# C210_0006_Power.net
KiCad netlist of a schematic drawn in Altium Designer
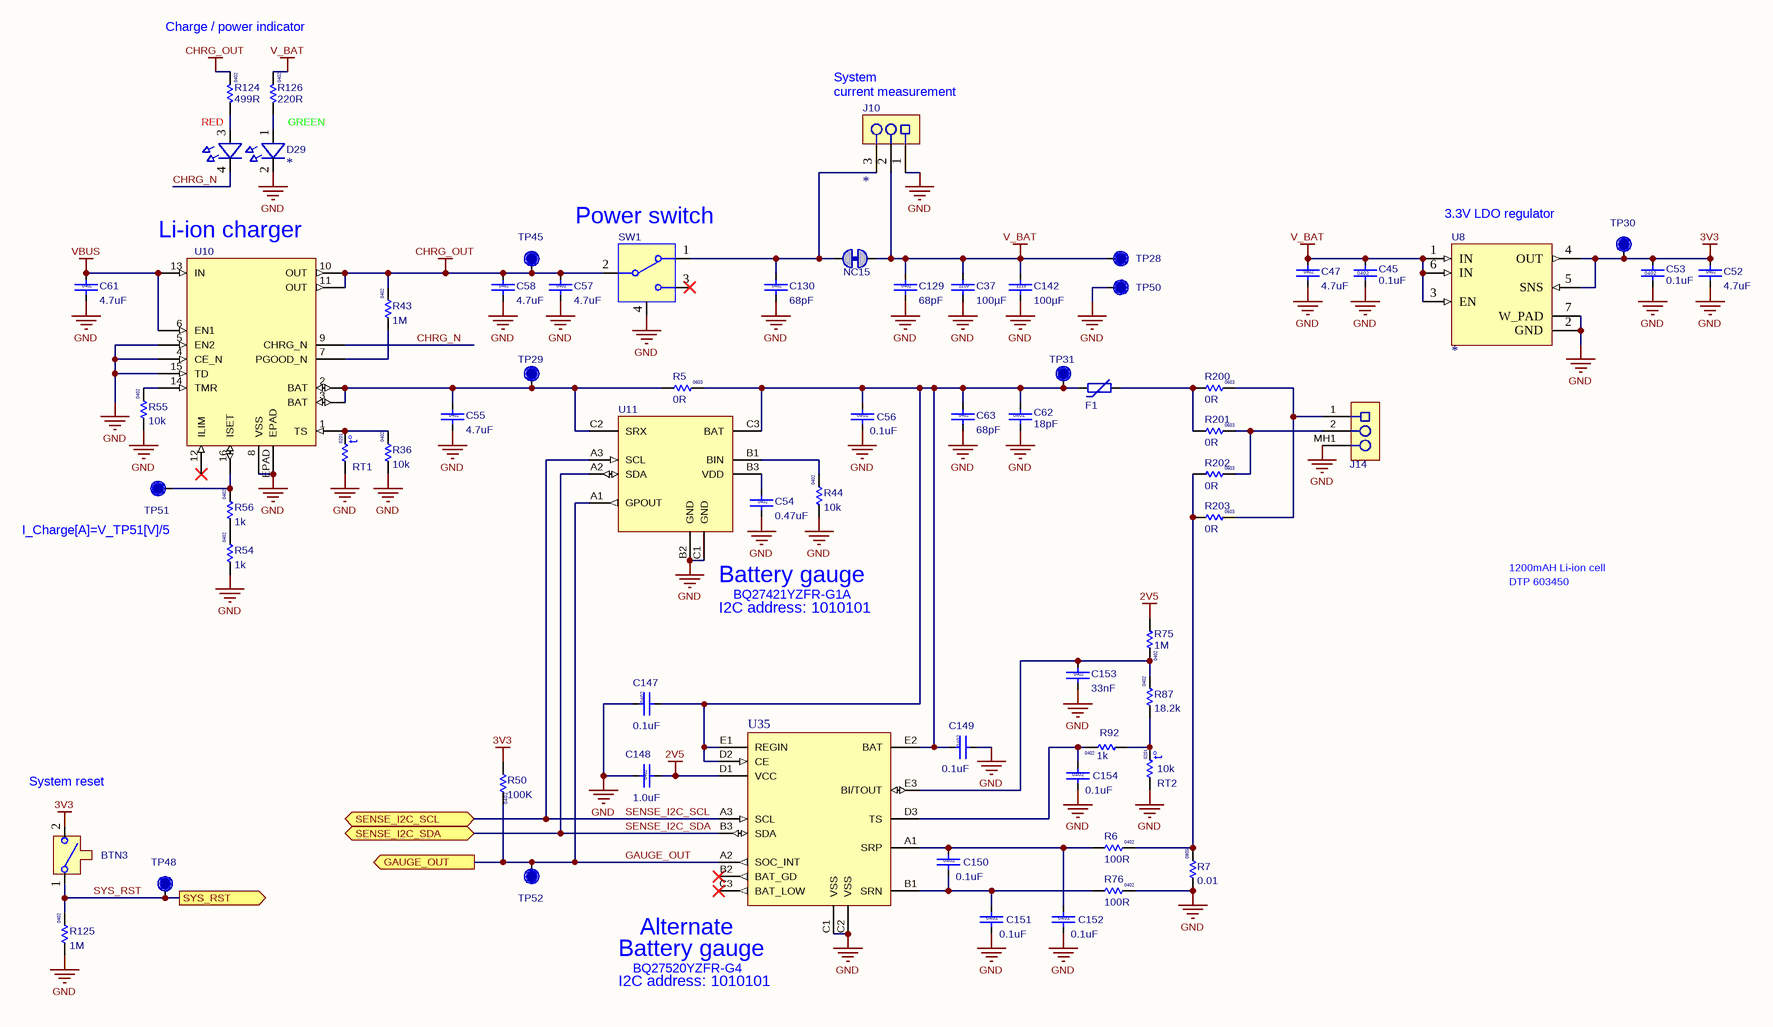
[diagram p0: C210_0006_Power.SchDoc]

(export (version "E")
  (design (tool "Eeschema 10.0.6"))
  (components
    (comp (ref "BTN3")
      (value "135-00006")
      (footprint "B3U-3000P")
      (description "Button SPST-NO Off-MOM, 50mA 12V, Right Angle, SMT")
      (fields (field (name "VOLTAGE") "12VDC"))
      (libsource (lib "Arena_Parts_DB_Lib") (part "SW_SPST"))
    )
    (comp (ref "C37")
      (value "100µF")
      (footprint "Cap 1210")
      (description "100µF ±20% 10V Ceramic Capacitor X5R 1210 (3225 Metric)")
      (fields
        (field (name "SIZE") "1210")
        (field (name "PART NUMBER") "120-00223")
        (field (name "TOLERANCE") "+/- 20%")
      )
      (libsource (lib "Arena_Parts_DB_Lib") (part "Cap Chip"))
    )
    (comp (ref "C45")
      (value "0.1uF")
      (footprint "Cap 0402 HD")
      (description "Cap, Ceramic 0.1uF 10V 10% X5R 0402")
      (fields
        (field (name "SIZE") "0402")
        (field (name "PART NUMBER") "120-00016")
        (field (name "MANUFACTURER") "Murata Electronics North America")
      )
      (libsource (lib "Arena_Parts_DB_Lib") (part "Cap Chip"))
    )
    (comp (ref "C47")
      (value "4.7uF")
      (footprint "Cap 0402 HD")
      (description "Cap, Ceramic 4.7uF 10V 20% X5R 0402")
      (fields
        (field (name "SIZE") "0402")
        (field (name "PART NUMBER") "120-00020")
        (field (name "TOLERANCE") "+/- 20%")
      )
      (libsource (lib "Arena_Parts_DB_Lib") (part "Cap Chip"))
    )
    (comp (ref "C52")
      (value "4.7uF")
      (footprint "Cap 0402 HD")
      (description "Cap, Ceramic 4.7uF 10V 20% X5R 0402")
      (fields
        (field (name "SIZE") "0402")
        (field (name "PART NUMBER") "120-00020")
        (field (name "TOLERANCE") "+/- 20%")
      )
      (libsource (lib "Arena_Parts_DB_Lib") (part "Cap Chip"))
    )
    (comp (ref "C53")
      (value "0.1uF")
      (footprint "Cap 0402 HD")
      (description "Cap, Ceramic 0.1uF 10V 10% X5R 0402")
      (fields
        (field (name "SIZE") "0402")
        (field (name "PART NUMBER") "120-00016")
        (field (name "MANUFACTURER") "Murata Electronics North America")
      )
      (libsource (lib "Arena_Parts_DB_Lib") (part "Cap Chip"))
    )
    (comp (ref "C54")
      (value "0.47uF")
      (footprint "Cap 0402 HD")
      (description "Cap, Ceramic, 0.47UF 10V 10% X5R 0402")
      (fields
        (field (name "SIZE") "0402")
        (field (name "PART NUMBER") "120-00072")
        (field (name "TOLERANCE") "+/- 10%")
      )
      (libsource (lib "Arena_Parts_DB_Lib") (part "Cap Chip"))
    )
    (comp (ref "C55")
      (value "4.7uF")
      (footprint "Cap 0402 HD")
      (description "Cap, Ceramic 4.7uF 10V 20% X5R 0402")
      (fields
        (field (name "SIZE") "0402")
        (field (name "PART NUMBER") "120-00020")
        (field (name "TOLERANCE") "+/- 20%")
      )
      (libsource (lib "Arena_Parts_DB_Lib") (part "Cap Chip"))
    )
    (comp (ref "C56")
      (value "0.1uF")
      (footprint "Cap 0402 HD")
      (description "Cap, Ceramic 0.1uF 10V 10% X5R 0402")
      (fields
        (field (name "SIZE") "0402")
        (field (name "PART NUMBER") "120-00016")
        (field (name "MANUFACTURER") "Murata Electronics North America")
      )
      (libsource (lib "Arena_Parts_DB_Lib") (part "Cap Chip"))
    )
    (comp (ref "C57")
      (value "4.7uF")
      (footprint "Cap 0402 HD")
      (description "Cap, Ceramic 4.7uF 10V 20% X5R 0402")
      (fields
        (field (name "SIZE") "0402")
        (field (name "PART NUMBER") "120-00020")
        (field (name "TOLERANCE") "+/- 20%")
      )
      (libsource (lib "Arena_Parts_DB_Lib") (part "Cap Chip"))
    )
    (comp (ref "C58")
      (value "4.7uF")
      (footprint "Cap 0402 HD")
      (description "Cap, Ceramic 4.7uF 10V 20% X5R 0402")
      (fields
        (field (name "SIZE") "0402")
        (field (name "PART NUMBER") "120-00020")
        (field (name "TOLERANCE") "+/- 20%")
      )
      (libsource (lib "Arena_Parts_DB_Lib") (part "Cap Chip"))
    )
    (comp (ref "C61")
      (value "4.7uF")
      (footprint "Cap 0402 HD")
      (description "Cap, Ceramic 4.7uF 10V 20% X5R 0402")
      (fields
        (field (name "SIZE") "0402")
        (field (name "PART NUMBER") "120-00020")
        (field (name "TOLERANCE") "+/- 20%")
      )
      (libsource (lib "Arena_Parts_DB_Lib") (part "Cap Chip"))
    )
    (comp (ref "C62")
      (value "18pF")
      (footprint "Cap 0402 HD")
      (description "Cap, Ceramic 18pF 50V 5% NP0 0402")
      (fields
        (field (name "SIZE") "0402")
        (field (name "PART NUMBER") "120-00041")
        (field (name "TOLERANCE") "+/- 5%")
      )
      (libsource (lib "Arena_Parts_DB_Lib") (part "Cap Chip"))
    )
    (comp (ref "C63")
      (value "68pF")
      (footprint "Cap 0402 HD")
      (description "Cap, Ceramic, 68pF, 50V, 1%, NP0, 0402")
      (fields
        (field (name "SIZE") "0402")
        (field (name "PART NUMBER") "120-00047")
        (field (name "TOLERANCE") "+/- 1%")
      )
      (libsource (lib "Arena_Parts_DB_Lib") (part "Cap Chip"))
    )
    (comp (ref "C129")
      (value "68pF")
      (footprint "Cap 0402 HD")
      (description "Cap, Ceramic, 68pF, 50V, 1%, NP0, 0402")
      (fields
        (field (name "SIZE") "0402")
        (field (name "PART NUMBER") "120-00047")
        (field (name "TOLERANCE") "+/- 1%")
      )
      (libsource (lib "Arena_Parts_DB_Lib") (part "Cap Chip"))
    )
    (comp (ref "C130")
      (value "68pF")
      (footprint "Cap 0402 HD")
      (description "Cap, Ceramic, 68pF, 50V, 1%, NP0, 0402")
      (fields
        (field (name "SIZE") "0402")
        (field (name "PART NUMBER") "120-00047")
        (field (name "TOLERANCE") "+/- 1%")
      )
      (libsource (lib "Arena_Parts_DB_Lib") (part "Cap Chip"))
    )
    (comp (ref "C142")
      (value "100µF")
      (footprint "Cap 1210")
      (description "100µF ±20% 10V Ceramic Capacitor X5R 1210 (3225 Metric)")
      (fields
        (field (name "SIZE") "1210")
        (field (name "PART NUMBER") "120-00223")
        (field (name "TOLERANCE") "+/- 20%")
      )
      (libsource (lib "Arena_Parts_DB_Lib") (part "Cap Chip"))
    )
    (comp (ref "C147")
      (value "0.1uF")
      (footprint "Cap 0402 HD")
      (description "Cap, Ceramic 0.1uF 10V 10% X5R 0402")
      (fields
        (field (name "SIZE") "0402")
        (field (name "PART NUMBER") "120-00016")
        (field (name "MANUFACTURER") "Murata Electronics North America")
      )
      (libsource (lib "Arena_Parts_DB_Lib") (part "Cap Chip"))
    )
    (comp (ref "C148")
      (value "1.0uF")
      (footprint "Cap 0402 HD")
      (description "Cap, Ceramic, 1.0uF 10V 10% X5R, 0402")
      (fields
        (field (name "SIZE") "0402")
        (field (name "PART NUMBER") "120-00017")
        (field (name "MANUFACTURER") "Murata Electronics North America")
      )
      (libsource (lib "Arena_Parts_DB_Lib") (part "Cap Chip"))
    )
    (comp (ref "C149")
      (value "0.1uF")
      (footprint "Cap 0402 HD")
      (description "Cap, Ceramic 0.1uF 10V 10% X5R 0402")
      (fields
        (field (name "SIZE") "0402")
        (field (name "PART NUMBER") "120-00016")
        (field (name "MANUFACTURER") "Murata Electronics North America")
      )
      (libsource (lib "Arena_Parts_DB_Lib") (part "Cap Chip"))
    )
    (comp (ref "C150")
      (value "0.1uF")
      (footprint "Cap 0402 HD")
      (description "Cap, Ceramic 0.1uF 10V 10% X5R 0402")
      (fields
        (field (name "SIZE") "0402")
        (field (name "PART NUMBER") "120-00016")
        (field (name "MANUFACTURER") "Murata Electronics North America")
      )
      (libsource (lib "Arena_Parts_DB_Lib") (part "Cap Chip"))
    )
    (comp (ref "C151")
      (value "0.1uF")
      (footprint "Cap 0402 HD")
      (description "Cap, Ceramic 0.1uF 10V 10% X5R 0402")
      (fields
        (field (name "SIZE") "0402")
        (field (name "PART NUMBER") "120-00016")
        (field (name "MANUFACTURER") "Murata Electronics North America")
      )
      (libsource (lib "Arena_Parts_DB_Lib") (part "Cap Chip"))
    )
    (comp (ref "C152")
      (value "0.1uF")
      (footprint "Cap 0402 HD")
      (description "Cap, Ceramic 0.1uF 10V 10% X5R 0402")
      (fields
        (field (name "SIZE") "0402")
        (field (name "PART NUMBER") "120-00016")
        (field (name "MANUFACTURER") "Murata Electronics North America")
      )
      (libsource (lib "Arena_Parts_DB_Lib") (part "Cap Chip"))
    )
    (comp (ref "C153")
      (value "33nF")
      (footprint "Cap 0402 HD")
      (description "Cap, Ceramic 33nF 16V 10% X7R 0402")
      (fields
        (field (name "SIZE") "0402")
        (field (name "PART NUMBER") "120-00080")
        (field (name "TOLERANCE") "+/- 10%")
      )
      (libsource (lib "Arena_Parts_DB_Lib") (part "Cap Chip"))
    )
    (comp (ref "C154")
      (value "0.1uF")
      (footprint "Cap 0402 HD")
      (description "Cap, Ceramic 0.1uF 10V 10% X5R 0402")
      (fields
        (field (name "SIZE") "0402")
        (field (name "PART NUMBER") "120-00016")
        (field (name "MANUFACTURER") "Murata Electronics North America")
      )
      (libsource (lib "Arena_Parts_DB_Lib") (part "Cap Chip"))
    )
    (comp (ref "D29")
      (value "115-00013")
      (footprint "LED_4Pin_4213_RA_3215")
      (description "Dual LED, Red/Green, Right Angle, Dome 1208")
      (fields (field (name "COLOR") "*") (field (name "VOLTAGE") "None"))
      (libsource (lib "Arena_Parts_DB_Lib") (part "LED_Dual_1"))
    )
    (comp (ref "F1")
      (value "190-00005")
      (footprint "Fuse 1206")
      (description "Fuse, PTC 8V, 750mA, hold, 1.5A trip, 1206")
      (fields (field (name "VOLTAGE") "None"))
      (libsource (lib "Arena_Parts_DB_Lib") (part "PTC_Fuse"))
    )
    (comp (ref "J10")
      (value "130-00105")
      (footprint "HDR-0.1P-3Pin-1Row-SMT")
      (description "Header, 0.100\" Pitch, 3 Pin, Vertical SMT, Black")
      (fields (field (name "MANUFACTURER P/N") "*") (field (name "VOLTAGE") "None"))
      (libsource (lib "Arena_Parts_DB_Lib") (part "CON-3Pin_1Row"))
    )
    (comp (ref "J14")
      (value "S2B-PH-SM4-TB")
      (footprint "S2B-PH-SM4-TB")
      (description "Conn, SMT, 0.079\" Pitch, 2 Pin, R/A, Black")
      (fields (field (name "VOLTAGE") "None"))
      (libsource (lib "S2B-PH-SM4-TB") (part "S2B-PH-SM4-TB"))
    )
    (comp (ref "NC15")
      (value "Solderbridge-ShortDNP")
      (footprint "Solderbridge-Short")
      (description "Solderbridge-Short")
      (fields (field (name "ADDED BY") "Paul B"))
      (libsource (lib "PCB_Misc") (part "Solderbridge-Short"))
    )
    (comp (ref "R5")
      (value "0R")
      (footprint "RES 0603 HD")
      (description "Resistor 0 ohm Jumper, 1/10W, 0603")
      (fields
        (field (name "SIZE") "0603")
        (field (name "PART NUMBER") "180-00012")
        (field (name "POWER") "1/10W")
      )
      (libsource (lib "Arena_Parts_DB_Lib") (part "Res sm"))
    )
    (comp (ref "R6")
      (value "100R")
      (footprint "RES 0402 HD")
      (description "Resistor, 100ohm, 1%, 1/16W, 0402.")
      (fields
        (field (name "SIZE") "0402")
        (field (name "PART NUMBER") "180-00051")
        (field (name "POWER") "1/16W")
      )
      (libsource (lib "Arena_Parts_DB_Lib") (part "Res sm"))
    )
    (comp (ref "R7")
      (value "0.01")
      (footprint "RES 0805")
      (description "Resistor, 0.01 ohm 1% 1/2W, 0805")
      (fields (field (name "SIZE") "0805") (field (name "POWER") "1/2W") (field (name "TOLERANCE") "+/- 1%"))
      (libsource (lib "Arena_Parts_DB_Lib") (part "Res sm"))
    )
    (comp (ref "R36")
      (value "10k")
      (footprint "RES 0402 HD")
      (description "Resistor 10k ohm 1% 1/16W, 0402")
      (fields
        (field (name "SIZE") "0402")
        (field (name "PART NUMBER") "180-00024")
        (field (name "POWER") "1/16W")
      )
      (libsource (lib "Arena_Parts_DB_Lib") (part "Res sm"))
    )
    (comp (ref "R43")
      (value "1M")
      (footprint "RES 0402 HD")
      (description "Resistor 1M ohm 1%, 1/16W, 0402")
      (fields
        (field (name "SIZE") "0402")
        (field (name "PART NUMBER") "180-00054")
        (field (name "POWER") "1/16W")
      )
      (libsource (lib "Arena_Parts_DB_Lib") (part "Res sm"))
    )
    (comp (ref "R44")
      (value "10k")
      (footprint "RES 0402 HD")
      (description "Resistor 10k ohm 1% 1/16W, 0402")
      (fields
        (field (name "SIZE") "0402")
        (field (name "PART NUMBER") "180-00024")
        (field (name "POWER") "1/16W")
      )
      (libsource (lib "Arena_Parts_DB_Lib") (part "Res sm"))
    )
    (comp (ref "R50")
      (value "100K")
      (footprint "RES 0402 HD")
      (description "Resistor 100K ohm 1% 1/16W, 0402")
      (fields
        (field (name "SIZE") "0402")
        (field (name "PART NUMBER") "180-00093")
        (field (name "POWER") "1/16W")
      )
      (libsource (lib "Arena_Parts_DB_Lib") (part "Res sm"))
    )
    (comp (ref "R54")
      (value "1k")
      (footprint "RES 0402 HD")
      (description "Resistor 1k ohm 1% 1/16W, 0402")
      (fields
        (field (name "SIZE") "0402")
        (field (name "PART NUMBER") "180-00021")
        (field (name "POWER") "1/16W")
      )
      (libsource (lib "Arena_Parts_DB_Lib") (part "Res sm"))
    )
    (comp (ref "R55")
      (value "10k")
      (footprint "RES 0402 HD")
      (description "Resistor 10k ohm 1% 1/16W, 0402")
      (fields
        (field (name "SIZE") "0402")
        (field (name "PART NUMBER") "180-00024")
        (field (name "POWER") "1/16W")
      )
      (libsource (lib "Arena_Parts_DB_Lib") (part "Res sm"))
    )
    (comp (ref "R56")
      (value "1k")
      (footprint "RES 0402 HD")
      (description "Resistor 1k ohm 1% 1/16W, 0402")
      (fields
        (field (name "SIZE") "0402")
        (field (name "PART NUMBER") "180-00021")
        (field (name "POWER") "1/16W")
      )
      (libsource (lib "Arena_Parts_DB_Lib") (part "Res sm"))
    )
    (comp (ref "R75")
      (value "1M")
      (footprint "RES 0402 HD")
      (description "Resistor 1M ohm 1%, 1/16W, 0402")
      (fields
        (field (name "SIZE") "0402")
        (field (name "PART NUMBER") "180-00054")
        (field (name "POWER") "1/16W")
      )
      (libsource (lib "Arena_Parts_DB_Lib") (part "Res sm"))
    )
    (comp (ref "R76")
      (value "100R")
      (footprint "RES 0402 HD")
      (description "Resistor, 100ohm, 1%, 1/16W, 0402.")
      (fields
        (field (name "SIZE") "0402")
        (field (name "PART NUMBER") "180-00051")
        (field (name "POWER") "1/16W")
      )
      (libsource (lib "Arena_Parts_DB_Lib") (part "Res sm"))
    )
    (comp (ref "R87")
      (value "18.2k")
      (footprint "RES 0402 HD")
      (description "Resistor, 18.2KOhm, 1%, 1/16W, 0402")
      (fields (field (name "SIZE") "0402") (field (name "POWER") "1/16W") (field (name "TOLERANCE") "+/- 1%"))
      (libsource (lib "Arena_Parts_DB_Lib") (part "Res sm"))
    )
    (comp (ref "R92")
      (value "1k")
      (footprint "RES 0402 HD")
      (description "Resistor 1k ohm 1% 1/16W, 0402")
      (fields
        (field (name "SIZE") "0402")
        (field (name "PART NUMBER") "180-00021")
        (field (name "POWER") "1/16W")
      )
      (libsource (lib "Arena_Parts_DB_Lib") (part "Res sm"))
    )
    (comp (ref "R124")
      (value "499R")
      (footprint "RES 0402 HD")
      (description "Resistor, 499ohm, 1%, 1/16W, 0402")
      (fields
        (field (name "SIZE") "0402")
        (field (name "PART NUMBER") "180-00031")
        (field (name "MANUFACTURER") "Rohm Semiconductor")
      )
      (libsource (lib "Arena_Parts_DB_Lib") (part "Res sm"))
    )
    (comp (ref "R125")
      (value "1M")
      (footprint "RES 0402 HD")
      (description "Resistor 1M ohm 1%, 1/16W, 0402")
      (fields
        (field (name "SIZE") "0402")
        (field (name "PART NUMBER") "180-00054")
        (field (name "POWER") "1/16W")
      )
      (libsource (lib "Arena_Parts_DB_Lib") (part "Res sm"))
    )
    (comp (ref "R126")
      (value "220R")
      (footprint "RES 0402 HD")
      (description "Resistor, 220ohm, 5%, 1/16W, 0402.")
      (fields
        (field (name "SIZE") "0402")
        (field (name "PART NUMBER") "180-00098")
        (field (name "MANUFACTURER") "Panasonic Electronic Components")
      )
      (libsource (lib "Arena_Parts_DB_Lib") (part "Res sm"))
    )
    (comp (ref "R200")
      (value "0R")
      (footprint "RES 0603 HD")
      (description "Resistor 0 ohm Jumper, 1/10W, 0603")
      (fields
        (field (name "SIZE") "0603")
        (field (name "PART NUMBER") "180-00012")
        (field (name "POWER") "1/10W")
      )
      (libsource (lib "Arena_Parts_DB_Lib") (part "Res sm"))
    )
    (comp (ref "R201")
      (value "0R")
      (footprint "RES 0603 HD")
      (description "Resistor 0 ohm Jumper, 1/10W, 0603")
      (fields
        (field (name "SIZE") "0603")
        (field (name "PART NUMBER") "180-00012")
        (field (name "POWER") "1/10W")
      )
      (libsource (lib "Arena_Parts_DB_Lib") (part "Res sm"))
    )
    (comp (ref "R202")
      (value "0R")
      (footprint "RES 0603 HD")
      (description "Resistor 0 ohm Jumper, 1/10W, 0603")
      (fields
        (field (name "SIZE") "0603")
        (field (name "PART NUMBER") "180-00012")
        (field (name "POWER") "1/10W")
      )
      (libsource (lib "Arena_Parts_DB_Lib") (part "Res sm"))
    )
    (comp (ref "R203")
      (value "0R")
      (footprint "RES 0603 HD")
      (description "Resistor 0 ohm Jumper, 1/10W, 0603")
      (fields
        (field (name "SIZE") "0603")
        (field (name "PART NUMBER") "180-00012")
        (field (name "POWER") "1/10W")
      )
      (libsource (lib "Arena_Parts_DB_Lib") (part "Res sm"))
    )
    (comp (ref "RT1")
      (value "Res Thermal")
      (footprint "RES 0201 HD")
      (description "Thermistor, 10Kohm, NTC 5%, 0201, 0.6mm x 0.3mm")
      (fields
        (field (name "SIZE") "0201")
        (field (name "PART NUMBER") "182-00002")
        (field (name "POWER") "1/20W")
      )
      (libsource (lib "Arena_Parts_DB_Lib") (part "Res Thermal"))
    )
    (comp (ref "RT2")
      (value "10k")
      (footprint "RES 0201 HD")
      (description "Thermistor, 10Kohm, NTC 5%, 0201, 0.6mm x 0.3mm")
      (fields
        (field (name "SIZE") "0201")
        (field (name "PART NUMBER") "182-00002")
        (field (name "POWER") "1/20W")
      )
      (libsource (lib "Arena_Parts_DB_Lib") (part "Res Thermal"))
    )
    (comp (ref "SW1")
      (value "137-00002")
      (footprint "EG1224")
      (description "Slide switch, SPDT, 3 Pin, 500mA, 15V, Through Hole")
      (fields (field (name "VOLTAGE") "15V"))
      (libsource (lib "Arena_Parts_DB_Lib") (part "SW_SPDT_Shield"))
    )
    (comp (ref "TP28")
      (value "TP")
      (footprint "TP12R")
      (description "Testpoint, Round 1.0mm Dia")
      (fields
        (field (name "PART NUMBER") "TP10R")
        (field (name "ADDED BY") "Jeremy D")
        (field (name "CHECKED BY") "Paul B")
      )
      (libsource (lib "PCB_Misc") (part "TP_R"))
    )
    (comp (ref "TP29")
      (value "TP")
      (footprint "TP12R")
      (description "Testpoint, Round 1.0mm Dia")
      (fields
        (field (name "PART NUMBER") "TP10R")
        (field (name "ADDED BY") "Jeremy D")
        (field (name "CHECKED BY") "Paul B")
      )
      (libsource (lib "PCB_Misc") (part "TP_R"))
    )
    (comp (ref "TP30")
      (value "TP")
      (footprint "TP12R")
      (description "Testpoint, Round 1.0mm Dia")
      (fields
        (field (name "PART NUMBER") "TP10R")
        (field (name "ADDED BY") "Jeremy D")
        (field (name "CHECKED BY") "Paul B")
      )
      (libsource (lib "PCB_Misc") (part "TP_R"))
    )
    (comp (ref "TP31")
      (value "TP")
      (footprint "TP12R")
      (description "Testpoint, Round 1.0mm Dia")
      (fields
        (field (name "PART NUMBER") "TP10R")
        (field (name "ADDED BY") "Jeremy D")
        (field (name "CHECKED BY") "Paul B")
      )
      (libsource (lib "PCB_Misc") (part "TP_R"))
    )
    (comp (ref "TP45")
      (value "TP")
      (footprint "TP12R")
      (description "Testpoint, Round 1.0mm Dia")
      (fields
        (field (name "PART NUMBER") "TP10R")
        (field (name "ADDED BY") "Jeremy D")
        (field (name "CHECKED BY") "Paul B")
      )
      (libsource (lib "PCB_Misc") (part "TP_R"))
    )
    (comp (ref "TP48")
      (value "TP")
      (footprint "TP12R")
      (description "Testpoint, Round 1.0mm Dia")
      (fields
        (field (name "PART NUMBER") "TP10R")
        (field (name "ADDED BY") "Jeremy D")
        (field (name "CHECKED BY") "Paul B")
      )
      (libsource (lib "PCB_Misc") (part "TP_R"))
    )
    (comp (ref "TP50")
      (value "TP")
      (footprint "TP12R")
      (description "Testpoint, Round 1.0mm Dia")
      (fields
        (field (name "PART NUMBER") "TP10R")
        (field (name "ADDED BY") "Jeremy D")
        (field (name "CHECKED BY") "Paul B")
      )
      (libsource (lib "PCB_Misc") (part "TP_R"))
    )
    (comp (ref "TP51")
      (value "TP")
      (footprint "TP12R")
      (description "Testpoint, Round 1.0mm Dia")
      (fields
        (field (name "PART NUMBER") "TP10R")
        (field (name "ADDED BY") "Jeremy D")
        (field (name "CHECKED BY") "Paul B")
      )
      (libsource (lib "PCB_Misc") (part "TP_R"))
    )
    (comp (ref "TP52")
      (value "TP")
      (footprint "TP12R")
      (description "Testpoint, Round 1.0mm Dia")
      (fields
        (field (name "PART NUMBER") "TP10R")
        (field (name "ADDED BY") "Jeremy D")
        (field (name "CHECKED BY") "Paul B")
      )
      (libsource (lib "PCB_Misc") (part "TP_R"))
    )
    (comp (ref "U8")
      (value "260-00045")
      (footprint "DFN0.95P-6Pin_W-Pad")
      (description "IC REG LDO 3.3V 1A 6DFN")
      (fields (field (name "MANUFACTURER P/N") "*") (field (name "VOLTAGE") "3.3V"))
      (libsource (lib "Arena_Parts_DB_Lib") (part "NCP692MN33T2G"))
    )
    (comp (ref "U10")
      (value "bq24230")
      (footprint "QFN0.5P3x3-16Pin_W-Pad")
      (description "BAT CHARGER, Li-ION, SMT, USB, PWR PATH, 500mA, 4.4V, 3mmx3mm QFN-16")
      (fields (field (name "VOLTAGE") "5-6.5V"))
      (libsource (lib "bq24230") (part "bq24230"))
    )
    (comp (ref "U11")
      (value "BQ27421YZFR-G1A")
      (footprint "BQ27421")
      (description "IC, SMT, BATTERY GAUGE, INGLE CELL Li-ION, COULOMB COUNTER, DSBGA-9 1.6mmX1.6mm")
      (libsource (lib "BQ27421") (part "BQ27421"))
    )
    (comp (ref "U35")
      (value "BQ27520YZFR-G4")
      (footprint "BQ27520")
      (description "IC, SMT, BATTERY GAUGE, INGLE CELL Li-ION, COULOMB COUNTER, DSBGA-15 2.6mmX2.0mm")
      (libsource (lib "BQ27520") (part "BQ27520"))
    )
  )
  (nets
    (net (code "1") (name "/CHRG_N") (class "Default")
      (node (ref "D29") (pin "4") (pinfunction "C2_4") (pintype "passive"))
      (node (ref "U10") (pin "9") (pinfunction "CHRG_N_9") (pintype "open_collector"))
    )
    (net (code "2") (name "/GAUGE_OUT") (class "Default")
      (node (ref "R50") (pin "2") (pinfunction "2_2") (pintype "passive"))
      (node (ref "TP52") (pin "1") (pintype "passive"))
      (node (ref "U11") (pin "A1") (pinfunction "GPOUT_A1") (pintype "output"))
      (node (ref "U35") (pin "A2") (pinfunction "SOC_INT_A2") (pintype "output"))
    )
    (net (code "3") (name "/SENSE_I2C_SCL") (class "Default")
      (node (ref "U11") (pin "A3") (pinfunction "SCL_A3") (pintype "input"))
      (node (ref "U35") (pin "A3") (pinfunction "SCL_A3") (pintype "input"))
    )
    (net (code "4") (name "/SENSE_I2C_SDA") (class "Default")
      (node (ref "U11") (pin "A2") (pinfunction "SDA_A2") (pintype "bidirectional"))
      (node (ref "U35") (pin "B3") (pinfunction "SDA_B3") (pintype "bidirectional"))
    )
    (net (code "5") (name "/SYS_RST") (class "Default")
      (node (ref "BTN3") (pin "1") (pinfunction "1_1") (pintype "passive"))
      (node (ref "R125") (pin "2") (pinfunction "2_2") (pintype "passive"))
      (node (ref "TP48") (pin "1") (pintype "passive"))
    )
    (net (code "6") (name "2V5") (class "Default")
      (node (ref "C148") (pin "2") (pinfunction "2_2") (pintype "passive"))
      (node (ref "R75") (pin "1") (pinfunction "1_1") (pintype "passive"))
      (node (ref "U35") (pin "D1") (pinfunction "VCC_D1") (pintype "passive"))
    )
    (net (code "7") (name "3V3") (class "Default")
      (node (ref "BTN3") (pin "2") (pinfunction "2_2") (pintype "passive"))
      (node (ref "C52") (pin "1") (pinfunction "1_1") (pintype "passive"))
      (node (ref "C53") (pin "2") (pinfunction "2_2") (pintype "passive"))
      (node (ref "R50") (pin "1") (pinfunction "1_1") (pintype "passive"))
      (node (ref "TP30") (pin "1") (pintype "passive"))
      (node (ref "U8") (pin "4") (pinfunction "OUT_4") (pintype "output"))
      (node (ref "U8") (pin "5") (pinfunction "SNS_5") (pintype "input"))
    )
    (net (code "8") (name "CHRG_OUT") (class "Default")
      (node (ref "C57") (pin "1") (pinfunction "1_1") (pintype "passive"))
      (node (ref "C58") (pin "1") (pinfunction "1_1") (pintype "passive"))
      (node (ref "R124") (pin "2") (pinfunction "2_2") (pintype "passive"))
      (node (ref "R43") (pin "2") (pinfunction "2_2") (pintype "passive"))
      (node (ref "SW1") (pin "2") (pinfunction "2_2") (pintype "passive"))
      (node (ref "TP45") (pin "1") (pintype "passive"))
      (node (ref "U10") (pin "10") (pinfunction "OUT_10") (pintype "output"))
      (node (ref "U10") (pin "11") (pinfunction "OUT_11") (pintype "output"))
    )
    (net (code "9") (name "GND") (class "Default")
      (node (ref "C129") (pin "2") (pinfunction "2_2") (pintype "passive"))
      (node (ref "C130") (pin "2") (pinfunction "2_2") (pintype "passive"))
      (node (ref "C142") (pin "2") (pinfunction "2_2") (pintype "passive"))
      (node (ref "C147") (pin "2") (pinfunction "2_2") (pintype "passive"))
      (node (ref "C148") (pin "1") (pinfunction "1_1") (pintype "passive"))
      (node (ref "C149") (pin "1") (pinfunction "1_1") (pintype "passive"))
      (node (ref "C151") (pin "1") (pinfunction "1_1") (pintype "passive"))
      (node (ref "C152") (pin "1") (pinfunction "1_1") (pintype "passive"))
      (node (ref "C153") (pin "2") (pinfunction "2_2") (pintype "passive"))
      (node (ref "C154") (pin "1") (pinfunction "1_1") (pintype "passive"))
      (node (ref "C37") (pin "2") (pinfunction "2_2") (pintype "passive"))
      (node (ref "C45") (pin "1") (pinfunction "1_1") (pintype "passive"))
      (node (ref "C47") (pin "2") (pinfunction "2_2") (pintype "passive"))
      (node (ref "C52") (pin "2") (pinfunction "2_2") (pintype "passive"))
      (node (ref "C53") (pin "1") (pinfunction "1_1") (pintype "passive"))
      (node (ref "C54") (pin "2") (pinfunction "2_2") (pintype "passive"))
      (node (ref "C55") (pin "2") (pinfunction "2_2") (pintype "passive"))
      (node (ref "C56") (pin "1") (pinfunction "1_1") (pintype "passive"))
      (node (ref "C57") (pin "2") (pinfunction "2_2") (pintype "passive"))
      (node (ref "C58") (pin "2") (pinfunction "2_2") (pintype "passive"))
      (node (ref "C61") (pin "2") (pinfunction "2_2") (pintype "passive"))
      (node (ref "C62") (pin "1") (pinfunction "1_1") (pintype "passive"))
      (node (ref "C63") (pin "2") (pinfunction "2_2") (pintype "passive"))
      (node (ref "D29") (pin "2") (pinfunction "C1_2") (pintype "passive"))
      (node (ref "J10") (pin "1") (pinfunction "1_1") (pintype "passive"))
      (node (ref "J14") (pin "MH1") (pinfunction "MH1_MH1") (pintype "passive"))
      (node (ref "R125") (pin "1") (pinfunction "1_1") (pintype "passive"))
      (node (ref "R36") (pin "1") (pinfunction "1_1") (pintype "passive"))
      (node (ref "R44") (pin "1") (pinfunction "1_1") (pintype "passive"))
      (node (ref "R54") (pin "1") (pinfunction "1_1") (pintype "passive"))
      (node (ref "R55") (pin "1") (pinfunction "1_1") (pintype "passive"))
      (node (ref "R7") (pin "1") (pinfunction "1_1") (pintype "passive"))
      (node (ref "R76") (pin "2") (pinfunction "2_2") (pintype "passive"))
      (node (ref "RT1") (pin "2") (pinfunction "2_2") (pintype "passive"))
      (node (ref "RT2") (pin "2") (pinfunction "2_2") (pintype "passive"))
      (node (ref "SW1") (pin "4") (pinfunction "GND_4") (pintype "power_in"))
      (node (ref "TP50") (pin "1") (pintype "passive"))
      (node (ref "U10") (pin "15") (pinfunction "TD_15") (pintype "input"))
      (node (ref "U10") (pin "4") (pinfunction "CE_N_4") (pintype "input"))
      (node (ref "U10") (pin "5") (pinfunction "EN2_5") (pintype "input"))
      (node (ref "U10") (pin "8") (pinfunction "VSS_8") (pintype "power_in"))
      (node (ref "U10") (pin "EPAD") (pinfunction "EPAD_EPAD") (pintype "power_in"))
      (node (ref "U11") (pin "B2") (pinfunction "GND_B2") (pintype "power_in"))
      (node (ref "U11") (pin "C1") (pinfunction "GND_C1") (pintype "power_in"))
      (node (ref "U35") (pin "C1") (pinfunction "VSS_C1") (pintype "power_in"))
      (node (ref "U35") (pin "C2") (pinfunction "VSS_C2") (pintype "power_in"))
      (node (ref "U8") (pin "2") (pinfunction "GND_2") (pintype "power_in"))
      (node (ref "U8") (pin "7") (pinfunction "W_PAD_7") (pintype "power_in"))
    )
    (net (code "10") (name "Net-(C130-Pad1)") (class "Default")
      (node (ref "C130") (pin "1") (pinfunction "1_1") (pintype "passive"))
      (node (ref "J10") (pin "3") (pinfunction "3_3") (pintype "passive"))
      (node (ref "NC15") (pin "2") (pinfunction "2_2") (pintype "passive"))
      (node (ref "SW1") (pin "1") (pinfunction "1_1") (pintype "passive"))
    )
    (net (code "11") (name "Net-(D29-A1)") (class "Default")
      (node (ref "D29") (pin "1") (pinfunction "A1_1") (pintype "passive"))
      (node (ref "R126") (pin "1") (pinfunction "1_1") (pintype "passive"))
    )
    (net (code "12") (name "Net-(D29-A2)") (class "Default")
      (node (ref "D29") (pin "3") (pinfunction "A2_3") (pintype "passive"))
      (node (ref "R124") (pin "1") (pinfunction "1_1") (pintype "passive"))
    )
    (net (code "13") (name "Net-(F1-Pad2)") (class "Default")
      (node (ref "F1") (pin "2") (pinfunction "2_2") (pintype "passive"))
      (node (ref "R200") (pin "1") (pinfunction "1_1") (pintype "passive"))
      (node (ref "R201") (pin "1") (pinfunction "1_1") (pintype "passive"))
    )
    (net (code "14") (name "Net-(J14-Pad1)") (class "Default")
      (node (ref "J14") (pin "1") (pinfunction "1_1") (pintype "passive"))
      (node (ref "R200") (pin "2") (pinfunction "2_2") (pintype "passive"))
      (node (ref "R203") (pin "2") (pinfunction "2_2") (pintype "passive"))
    )
    (net (code "15") (name "Net-(J14-Pad2)") (class "Default")
      (node (ref "J14") (pin "2") (pinfunction "2_2") (pintype "passive"))
      (node (ref "R201") (pin "2") (pinfunction "2_2") (pintype "passive"))
      (node (ref "R202") (pin "2") (pinfunction "2_2") (pintype "passive"))
    )
    (net (code "16") (name "Net-(R54-Pad2)") (class "Default")
      (node (ref "R54") (pin "2") (pinfunction "2_2") (pintype "passive"))
      (node (ref "R56") (pin "1") (pinfunction "1_1") (pintype "passive"))
    )
    (net (code "17") (name "Net-(R87-Pad1)") (class "Default")
      (node (ref "R87") (pin "1") (pinfunction "1_1") (pintype "passive"))
      (node (ref "R92") (pin "1") (pinfunction "1_1") (pintype "passive"))
      (node (ref "RT2") (pin "1") (pinfunction "1_1") (pintype "passive"))
    )
    (net (code "18") (name "Net-(R202-Pad1)") (class "Default")
      (node (ref "R202") (pin "1") (pinfunction "1_1") (pintype "passive"))
      (node (ref "R203") (pin "1") (pinfunction "1_1") (pintype "passive"))
      (node (ref "R6") (pin "2") (pinfunction "2_2") (pintype "passive"))
      (node (ref "R7") (pin "2") (pinfunction "2_2") (pintype "passive"))
    )
    (net (code "19") (name "Net-(U10-ISET)") (class "Default")
      (node (ref "R56") (pin "2") (pinfunction "2_2") (pintype "passive"))
      (node (ref "TP51") (pin "1") (pintype "passive"))
      (node (ref "U10") (pin "16") (pinfunction "ISET_16") (pintype "bidirectional"))
    )
    (net (code "20") (name "Net-(U10-PGOOD_N)") (class "Default")
      (node (ref "R43") (pin "1") (pinfunction "1_1") (pintype "passive"))
      (node (ref "U10") (pin "7") (pinfunction "PGOOD_N_7") (pintype "open_collector"))
    )
    (net (code "21") (name "Net-(U10-TMR)") (class "Default")
      (node (ref "R55") (pin "2") (pinfunction "2_2") (pintype "passive"))
      (node (ref "U10") (pin "14") (pinfunction "TMR_14") (pintype "input"))
    )
    (net (code "22") (name "Net-(U10-TS)") (class "Default")
      (node (ref "R36") (pin "2") (pinfunction "2_2") (pintype "passive"))
      (node (ref "RT1") (pin "1") (pinfunction "1_1") (pintype "passive"))
      (node (ref "U10") (pin "1") (pinfunction "TS_1") (pintype "input"))
    )
    (net (code "23") (name "Net-(U11-BAT)") (class "Default")
      (node (ref "C147") (pin "1") (pinfunction "1_1") (pintype "passive"))
      (node (ref "C149") (pin "2") (pinfunction "2_2") (pintype "passive"))
      (node (ref "C56") (pin "2") (pinfunction "2_2") (pintype "passive"))
      (node (ref "C62") (pin "2") (pinfunction "2_2") (pintype "passive"))
      (node (ref "C63") (pin "1") (pinfunction "1_1") (pintype "passive"))
      (node (ref "F1") (pin "1") (pinfunction "1_1") (pintype "passive"))
      (node (ref "R5") (pin "2") (pinfunction "2_2") (pintype "passive"))
      (node (ref "TP31") (pin "1") (pintype "passive"))
      (node (ref "U11") (pin "C3") (pinfunction "BAT_C3") (pintype "power_in"))
      (node (ref "U35") (pin "D2") (pinfunction "CE_D2") (pintype "input"))
      (node (ref "U35") (pin "E1") (pinfunction "REGIN_E1") (pintype "power_in"))
      (node (ref "U35") (pin "E2") (pinfunction "BAT_E2") (pintype "passive"))
    )
    (net (code "24") (name "Net-(U11-BIN)") (class "Default")
      (node (ref "R44") (pin "2") (pinfunction "2_2") (pintype "passive"))
      (node (ref "U11") (pin "B1") (pinfunction "BIN_B1") (pintype "power_in"))
    )
    (net (code "25") (name "Net-(U11-SRX)") (class "Default")
      (node (ref "C55") (pin "1") (pinfunction "1_1") (pintype "passive"))
      (node (ref "R5") (pin "1") (pinfunction "1_1") (pintype "passive"))
      (node (ref "TP29") (pin "1") (pintype "passive"))
      (node (ref "U10") (pin "2") (pinfunction "BAT_2") (pintype "bidirectional"))
      (node (ref "U10") (pin "3") (pinfunction "BAT_3") (pintype "bidirectional"))
      (node (ref "U11") (pin "C2") (pinfunction "SRX_C2") (pintype "passive"))
    )
    (net (code "26") (name "Net-(U11-VDD)") (class "Default")
      (node (ref "C54") (pin "1") (pinfunction "1_1") (pintype "passive"))
      (node (ref "U11") (pin "B3") (pinfunction "VDD_B3") (pintype "power_in"))
    )
    (net (code "27") (name "Net-(U35-BI{slash}TOUT)") (class "Default")
      (node (ref "C153") (pin "1") (pinfunction "1_1") (pintype "passive"))
      (node (ref "R75") (pin "2") (pinfunction "2_2") (pintype "passive"))
      (node (ref "R87") (pin "2") (pinfunction "2_2") (pintype "passive"))
      (node (ref "U35") (pin "E3") (pinfunction "BI/TOUT_E3") (pintype "bidirectional"))
    )
    (net (code "28") (name "Net-(U35-SRN)") (class "Default")
      (node (ref "C150") (pin "1") (pinfunction "1_1") (pintype "passive"))
      (node (ref "C151") (pin "2") (pinfunction "2_2") (pintype "passive"))
      (node (ref "R76") (pin "1") (pinfunction "1_1") (pintype "passive"))
      (node (ref "U35") (pin "B1") (pinfunction "SRN_B1") (pintype "passive"))
    )
    (net (code "29") (name "Net-(U35-SRP)") (class "Default")
      (node (ref "C150") (pin "2") (pinfunction "2_2") (pintype "passive"))
      (node (ref "C152") (pin "2") (pinfunction "2_2") (pintype "passive"))
      (node (ref "R6") (pin "1") (pinfunction "1_1") (pintype "passive"))
      (node (ref "U35") (pin "A1") (pinfunction "SRP_A1") (pintype "passive"))
    )
    (net (code "30") (name "Net-(U35-TS)") (class "Default")
      (node (ref "C154") (pin "2") (pinfunction "2_2") (pintype "passive"))
      (node (ref "R92") (pin "2") (pinfunction "2_2") (pintype "passive"))
      (node (ref "U35") (pin "D3") (pinfunction "TS_D3") (pintype "passive"))
    )
    (net (code "31") (name "VBUS") (class "Default")
      (node (ref "C61") (pin "1") (pinfunction "1_1") (pintype "passive"))
      (node (ref "U10") (pin "13") (pinfunction "IN_13") (pintype "input"))
      (node (ref "U10") (pin "6") (pinfunction "EN1_6") (pintype "input"))
    )
    (net (code "32") (name "V_BAT") (class "Default")
      (node (ref "C129") (pin "1") (pinfunction "1_1") (pintype "passive"))
      (node (ref "C142") (pin "1") (pinfunction "1_1") (pintype "passive"))
      (node (ref "C37") (pin "1") (pinfunction "1_1") (pintype "passive"))
      (node (ref "C45") (pin "2") (pinfunction "2_2") (pintype "passive"))
      (node (ref "C47") (pin "1") (pinfunction "1_1") (pintype "passive"))
      (node (ref "J10") (pin "2") (pinfunction "2_2") (pintype "passive"))
      (node (ref "NC15") (pin "1") (pinfunction "1_1") (pintype "passive"))
      (node (ref "R126") (pin "2") (pinfunction "2_2") (pintype "passive"))
      (node (ref "TP28") (pin "1") (pintype "passive"))
      (node (ref "U8") (pin "1") (pinfunction "IN_1") (pintype "input"))
      (node (ref "U8") (pin "3") (pinfunction "EN_3") (pintype "input"))
      (node (ref "U8") (pin "6") (pinfunction "IN_6") (pintype "input"))
    )
    (net (code "33") (name "unconnected-(SW1-Pad3)") (class "Default")
      (node (ref "SW1") (pin "3") (pinfunction "3_3") (pintype "passive+no_connect"))
    )
    (net (code "34") (name "unconnected-(U10-ILIM-Pad12)") (class "Default")
      (node (ref "U10") (pin "12") (pinfunction "ILIM_12") (pintype "input+no_connect"))
    )
    (net (code "35") (name "unconnected-(U35-BAT_GD-PadB2)") (class "Default")
      (node (ref "U35") (pin "B2") (pinfunction "BAT_GD_B2") (pintype "output+no_connect"))
    )
    (net (code "36") (name "unconnected-(U35-BAT_LOW-PadC3)") (class "Default")
      (node (ref "U35") (pin "C3") (pinfunction "BAT_LOW_C3") (pintype "output+no_connect"))
    )
  )
)
